# Camera.net
KiCad netlist of a schematic drawn in Altium Designer
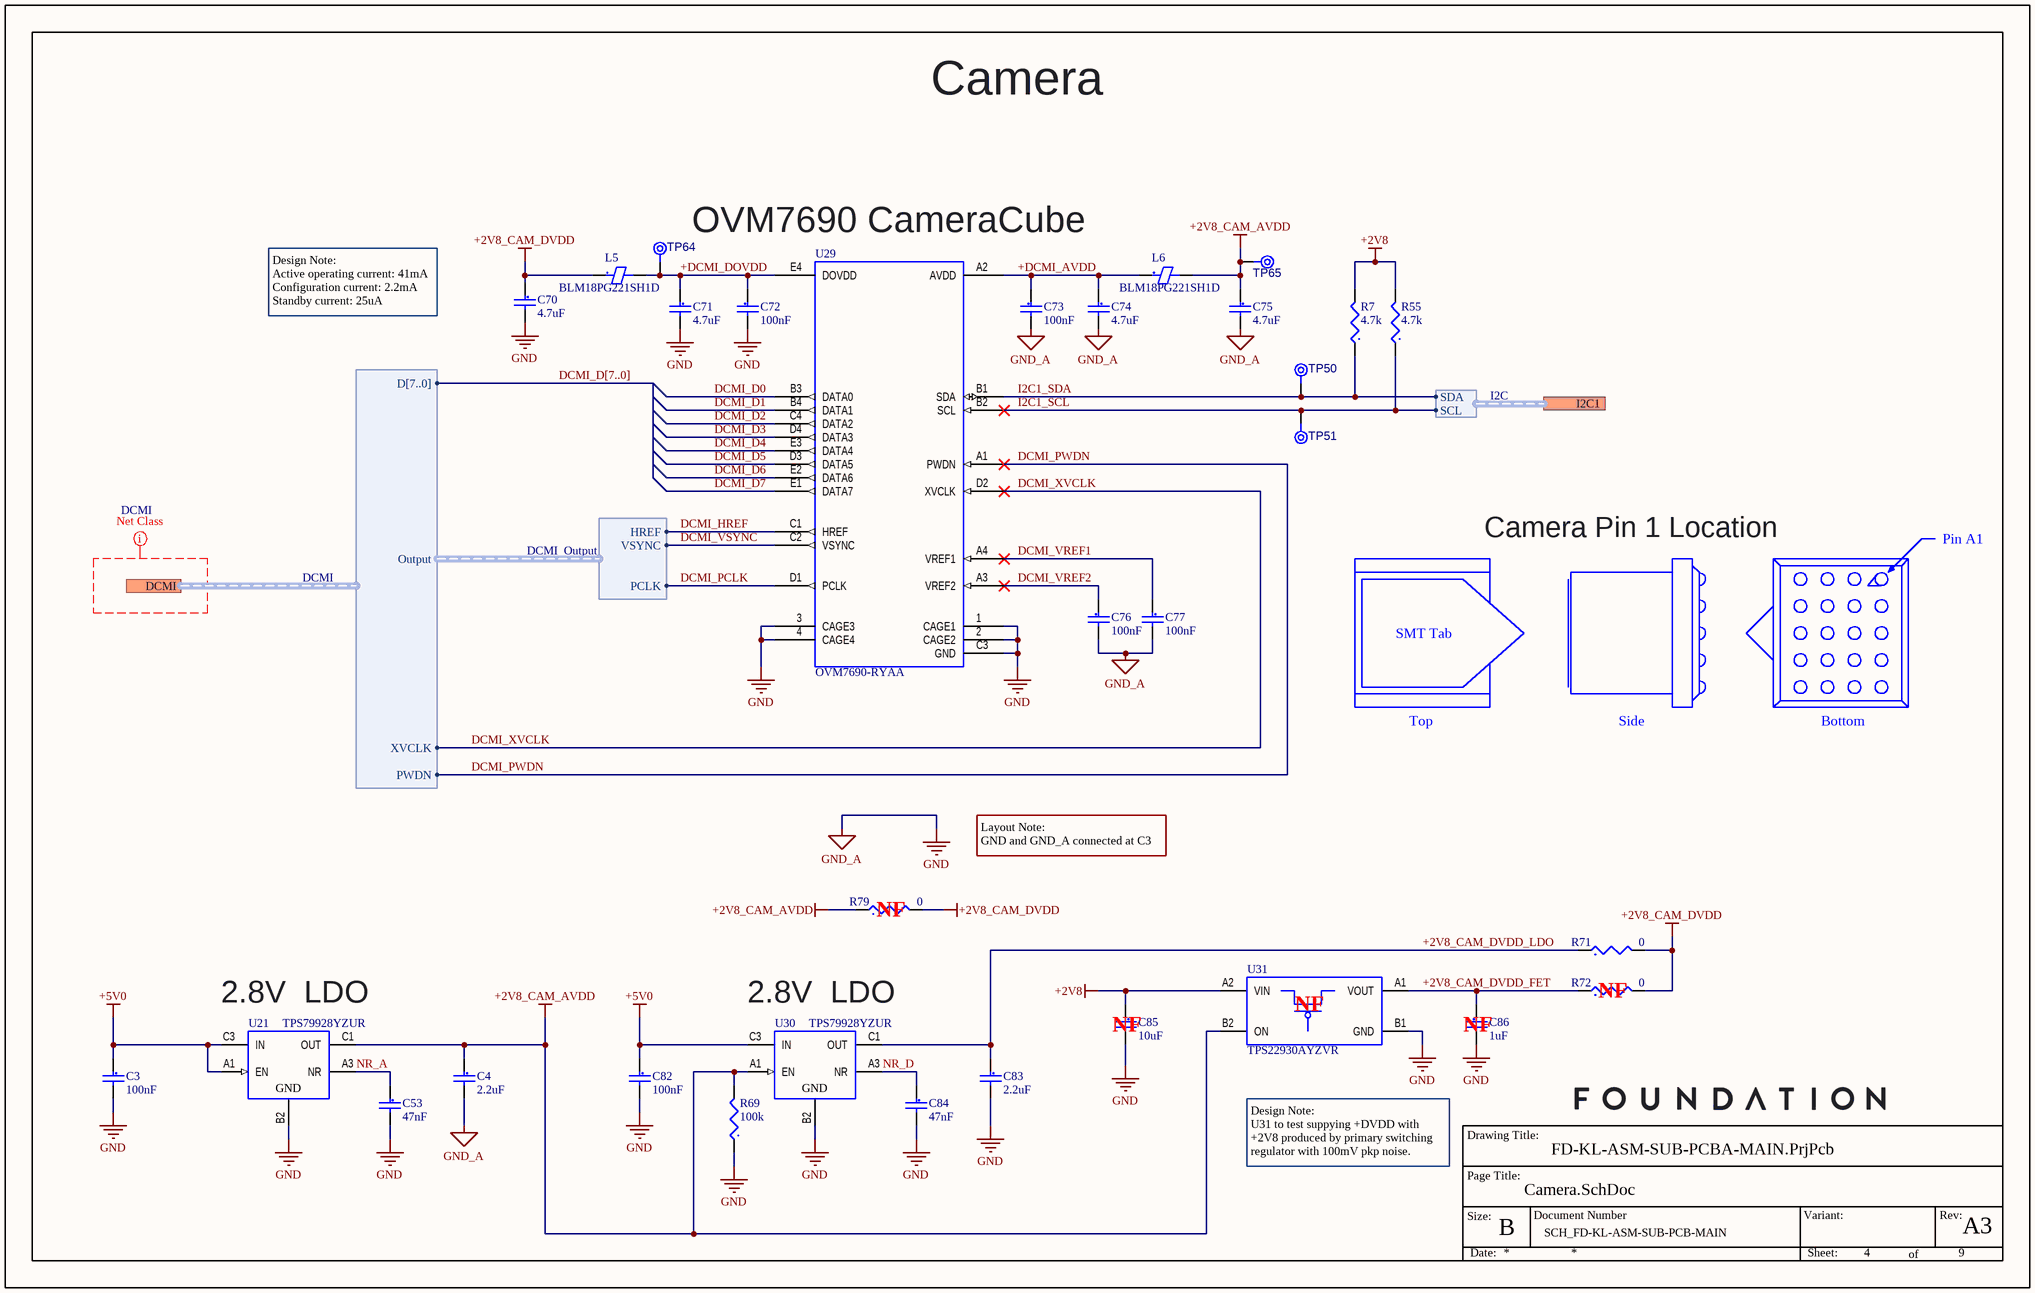
[diagram p0: Camera.SchDoc]

(export (version "E")
  (design (tool "Eeschema 10.0.6"))
  (components
    (comp (ref "C3")
      (value "CAP CER 0.1uF 16V 10% X7R 0402")
      (footprint "CAPC0402(1005)55_L")
      (description "0.1µF ±10% 16V Ceramic Capacitor X7R 0402 (1005 Metric)")
      (fields
        (field (name "CAPACITANCE") "100nF")
        (field (name "TOLERANCE") "10%")
        (field (name "VOLTAGE") "16V")
      )
      (libsource (lib "Altium Concord Pro on A365") (part "CAP-NP-2"))
    )
    (comp (ref "C4")
      (value "CAP CER 2.2uF 6.3V 10% X5R 0402")
      (footprint "CAPC0402(1005)55_L")
      (description "2.2µF ±10% 6.3V Ceramic Capacitor X5R 0402 (1005 Metric)")
      (fields (field (name "CAPACITANCE") "2.2uF") (field (name "TOLERANCE") "10%"))
      (libsource (lib "Altium Concord Pro on A365") (part "CAP-NP-2"))
    )
    (comp (ref "C53")
      (value "CAP CER 0.047uF 10V 10% X7R 0402")
      (footprint "CAPC0402(1005)55_L")
      (description "0.047µF ±10% 10V Ceramic Capacitor X7R 0402 (1005 Metric)")
      (fields (field (name "CAPACITANCE") "47nF"))
      (libsource (lib "Altium Concord Pro on A365") (part "CAP-NP-2"))
    )
    (comp (ref "C70")
      (value "CAP CER 4.7UF 10V 20% X5R 0402")
      (footprint "CAPC0402(1005)55_L")
      (description "4.7µF ±20% 10V Ceramic Capacitor X5R 0402 (1005 Metric)")
      (fields
        (field (name "CAPACITANCE") "4.7uF")
        (field (name "TOLERANCE") "20%")
        (field (name "VOLTAGE") "10V")
      )
      (libsource (lib "Altium Concord Pro on A365") (part "CAP-NP-2"))
    )
    (comp (ref "C71")
      (value "CAP CER 4.7UF 10V 20% X5R 0402")
      (footprint "CAPC0402(1005)55_L")
      (description "4.7µF ±20% 10V Ceramic Capacitor X5R 0402 (1005 Metric)")
      (fields
        (field (name "CAPACITANCE") "4.7uF")
        (field (name "TOLERANCE") "20%")
        (field (name "VOLTAGE") "10V")
      )
      (libsource (lib "Altium Concord Pro on A365") (part "CAP-NP-2"))
    )
    (comp (ref "C72")
      (value "CAP CER 0.1uF 16V 10% X7R 0402")
      (footprint "CAPC0402(1005)55_L")
      (description "0.1µF ±10% 16V Ceramic Capacitor X7R 0402 (1005 Metric)")
      (fields
        (field (name "CAPACITANCE") "100nF")
        (field (name "TOLERANCE") "10%")
        (field (name "VOLTAGE") "16V")
      )
      (libsource (lib "Altium Concord Pro on A365") (part "CAP-NP-2"))
    )
    (comp (ref "C73")
      (value "CAP CER 0.1uF 16V 10% X7R 0402")
      (footprint "CAPC0402(1005)55_L")
      (description "0.1µF ±10% 16V Ceramic Capacitor X7R 0402 (1005 Metric)")
      (fields
        (field (name "CAPACITANCE") "100nF")
        (field (name "TOLERANCE") "10%")
        (field (name "VOLTAGE") "16V")
      )
      (libsource (lib "Altium Concord Pro on A365") (part "CAP-NP-2"))
    )
    (comp (ref "C74")
      (value "CAP CER 4.7UF 10V 20% X5R 0402")
      (footprint "CAPC0402(1005)55_L")
      (description "4.7µF ±20% 10V Ceramic Capacitor X5R 0402 (1005 Metric)")
      (fields
        (field (name "CAPACITANCE") "4.7uF")
        (field (name "TOLERANCE") "20%")
        (field (name "VOLTAGE") "10V")
      )
      (libsource (lib "Altium Concord Pro on A365") (part "CAP-NP-2"))
    )
    (comp (ref "C75")
      (value "CAP CER 4.7UF 10V 20% X5R 0402")
      (footprint "CAPC0402(1005)55_L")
      (description "4.7µF ±20% 10V Ceramic Capacitor X5R 0402 (1005 Metric)")
      (fields
        (field (name "CAPACITANCE") "4.7uF")
        (field (name "TOLERANCE") "20%")
        (field (name "VOLTAGE") "10V")
      )
      (libsource (lib "Altium Concord Pro on A365") (part "CAP-NP-2"))
    )
    (comp (ref "C76")
      (value "CAP CER 0.1uF 16V 10% X7R 0402")
      (footprint "CAPC0402(1005)55_L")
      (description "0.1µF ±10% 16V Ceramic Capacitor X7R 0402 (1005 Metric)")
      (fields
        (field (name "CAPACITANCE") "100nF")
        (field (name "TOLERANCE") "10%")
        (field (name "VOLTAGE") "16V")
      )
      (libsource (lib "Altium Concord Pro on A365") (part "CAP-NP-2"))
    )
    (comp (ref "C77")
      (value "CAP CER 0.1uF 16V 10% X7R 0402")
      (footprint "CAPC0402(1005)55_L")
      (description "0.1µF ±10% 16V Ceramic Capacitor X7R 0402 (1005 Metric)")
      (fields
        (field (name "CAPACITANCE") "100nF")
        (field (name "TOLERANCE") "10%")
        (field (name "VOLTAGE") "16V")
      )
      (libsource (lib "Altium Concord Pro on A365") (part "CAP-NP-2"))
    )
    (comp (ref "C82")
      (value "CAP CER 0.1uF 16V 10% X7R 0402")
      (footprint "CAPC0402(1005)55_L")
      (description "0.1µF ±10% 16V Ceramic Capacitor X7R 0402 (1005 Metric)")
      (fields
        (field (name "CAPACITANCE") "100nF")
        (field (name "TOLERANCE") "10%")
        (field (name "VOLTAGE") "16V")
      )
      (libsource (lib "Altium Concord Pro on A365") (part "CAP-NP-2"))
    )
    (comp (ref "C83")
      (value "CAP CER 2.2uF 6.3V 10% X5R 0402")
      (footprint "CAPC0402(1005)55_L")
      (description "2.2µF ±10% 6.3V Ceramic Capacitor X5R 0402 (1005 Metric)")
      (fields (field (name "CAPACITANCE") "2.2uF") (field (name "TOLERANCE") "10%"))
      (libsource (lib "Altium Concord Pro on A365") (part "CAP-NP-2"))
    )
    (comp (ref "C84")
      (value "CAP CER 0.047uF 10V 10% X7R 0402")
      (footprint "CAPC0402(1005)55_L")
      (description "0.047µF ±10% 10V Ceramic Capacitor X7R 0402 (1005 Metric)")
      (fields (field (name "CAPACITANCE") "47nF"))
      (libsource (lib "Altium Concord Pro on A365") (part "CAP-NP-2"))
    )
    (comp (ref "C85")
      (value "CAP CER 10uF 10V 20% X5R 0402")
      (footprint "CAPC0402(1005)55_L")
      (description "10µF ±20% 10V Ceramic Capacitor X5R 0402 (1005 Metric)")
      (fields (field (name "CAPACITANCE") "10uF") (field (name "TOLERANCE") "20%"))
      (libsource (lib "Altium Concord Pro on A365") (part "CAP-NP-2"))
    )
    (comp (ref "C86")
      (value "CAP CER 1uF 25V 10% X5R 0402")
      (footprint "CAPC0402(1005)55_L")
      (description "1uF ±10% 25V Ceramic Capacitor X5R 0402 (1005 Metric)")
      (fields (field (name "CAPACITANCE") "1uF"))
      (libsource (lib "Altium Concord Pro on A365") (part "CAP-NP-2"))
    )
    (comp (ref "L5")
      (value "BLM18PG221SH1D")
      (footprint "FBC0603(1608)90_L")
      (description "FERRITE BEAD 220 OHM 0603 1LN")
      (fields (field (name "TOLERANCE") "25%"))
      (libsource (lib "Altium Concord Pro on A365") (part "FB-NP-2"))
    )
    (comp (ref "L6")
      (value "BLM18PG221SH1D")
      (footprint "FBC0603(1608)90_L")
      (description "FERRITE BEAD 220 OHM 0603 1LN")
      (fields (field (name "TOLERANCE") "25%"))
      (libsource (lib "Altium Concord Pro on A365") (part "FB-NP-2"))
    )
    (comp (ref "R7")
      (value "RES 4.7K 1/16W 1% 0402")
      (footprint "RESC0402(1005)_L")
      (description "4.7 kOhms ±1% 0.063W, 1/16W Chip Resistor 0402 (1005 Metric) Automotive AEC-Q200 Thick Film")
      (fields (field (name "RESISTANCE") "4.7k") (field (name "TOLERANCE") "1%"))
      (libsource (lib "Altium Concord Pro on A365") (part "RES-2"))
    )
    (comp (ref "R55")
      (value "RES 4.7K 1/16W 1% 0402")
      (footprint "RESC0402(1005)_L")
      (description "4.7 kOhms ±1% 0.063W, 1/16W Chip Resistor 0402 (1005 Metric) Automotive AEC-Q200 Thick Film")
      (fields (field (name "RESISTANCE") "4.7k") (field (name "TOLERANCE") "1%"))
      (libsource (lib "Altium Concord Pro on A365") (part "RES-2"))
    )
    (comp (ref "R69")
      (value "RES 100K 1/16W 1% 0402")
      (footprint "RESC0402(1005)_L")
      (description "100 kOhms ±1% 0.063W, 1/16W Chip Resistor 0402 (1005 Metric) Automotive AEC-Q200 Thick Film")
      (fields (field (name "RESISTANCE") "100k") (field (name "TOLERANCE") "1%"))
      (libsource (lib "Altium Concord Pro on A365") (part "RES-2"))
    )
    (comp (ref "R71")
      (value "RES 0 OHM JUMPER 1/10W 0603")
      (footprint "RESC0603(1608)_L")
      (description "0 Ohms Jumper 0.1W, 1/10W Chip Resistor 0603 (1608 Metric)")
      (fields (field (name "RESISTANCE") "0") (field (name "TOLERANCE") "1%"))
      (libsource (lib "Altium Concord Pro on A365") (part "RES-2"))
    )
    (comp (ref "R72")
      (value "RES 0 OHM JUMPER 1/10W 0603")
      (footprint "RESC0603(1608)_L")
      (description "0 Ohms Jumper 0.1W, 1/10W Chip Resistor 0603 (1608 Metric)")
      (fields (field (name "RESISTANCE") "0") (field (name "TOLERANCE") "1%"))
      (libsource (lib "Altium Concord Pro on A365") (part "RES-2"))
    )
    (comp (ref "R79")
      (value "RES 0 OHM JUMPER 1/10W 0603")
      (footprint "RESC0603(1608)_L")
      (description "0 Ohms Jumper 0.1W, 1/10W Chip Resistor 0603 (1608 Metric)")
      (fields (field (name "RESISTANCE") "0") (field (name "TOLERANCE") "1%"))
      (libsource (lib "Altium Concord Pro on A365") (part "RES-2"))
    )
    (comp (ref "TP50")
      (value "TPAD8R")
      (footprint "TP08R")
      (description "0.8mm round")
      (libsource (lib "Altium Concord Pro on A365") (part "TP-R-1"))
    )
    (comp (ref "TP51")
      (value "TPAD8R")
      (footprint "TP08R")
      (description "0.8mm round")
      (libsource (lib "Altium Concord Pro on A365") (part "TP-R-1"))
    )
    (comp (ref "TP64")
      (value "TPAD8R")
      (footprint "TP08R")
      (description "0.8mm round")
      (libsource (lib "Altium Concord Pro on A365") (part "TP-R-1"))
    )
    (comp (ref "TP65")
      (value "TPAD8R")
      (footprint "TP08R")
      (description "0.8mm round")
      (libsource (lib "Altium Concord Pro on A365") (part "TP-R-1"))
    )
    (comp (ref "U21")
      (value "TPS79928YZUR")
      (footprint "TI - DSBGA-YZU-5_V")
      (description "Linear Voltage Regulator IC  1 Output  200mA 5-DSBGA (1x1.37)")
      (libsource (lib "Altium Concord Pro on A365") (part "TPS79928YZU"))
    )
    (comp (ref "U29")
      (value "OVM7690-RYAA")
      (footprint "OMNI - CCBGA-CG-20")
      (description "SENSOR CAMERA CMOS 20CAMERACUBE")
      (libsource (lib "Altium Concord Pro on A365") (part "OVM7690-RYAA"))
    )
    (comp (ref "U30")
      (value "TPS79928YZUR")
      (footprint "TI - DSBGA-YZU-5_V")
      (description "Linear Voltage Regulator IC  1 Output  200mA 5-DSBGA (1x1.37)")
      (libsource (lib "Altium Concord Pro on A365") (part "TPS79928YZU"))
    )
    (comp (ref "U31")
      (value "TPS22930AYZVR")
      (footprint "TI - DSBGA-YZV-4_V")
      (description "IC PWR SWITCH P-CHAN 1:1 4DSBGA")
      (libsource (lib "Altium Concord Pro on A365") (part "TPS22930AYZVR"))
    )
  )
  (nets
    (net (code "4") (name "+2V8") (class "Default")
      (node (ref "C85") (pin "1") (pinfunction "1_1") (pintype "passive"))
      (node (ref "R55") (pin "2") (pinfunction "2_2") (pintype "passive"))
      (node (ref "R7") (pin "2") (pinfunction "2_2") (pintype "passive"))
      (node (ref "U31") (pin "A2") (pinfunction "VIN_A2") (pintype "passive"))
    )
    (net (code "5") (name "+2V8_CAM_AVDD") (class "Default")
      (node (ref "C4") (pin "1") (pinfunction "1_1") (pintype "passive"))
      (node (ref "C75") (pin "1") (pinfunction "1_1") (pintype "passive"))
      (node (ref "L6") (pin "2") (pinfunction "2_2") (pintype "passive"))
      (node (ref "R69") (pin "2") (pinfunction "2_2") (pintype "passive"))
      (node (ref "R79") (pin "1") (pinfunction "1_1") (pintype "passive"))
      (node (ref "TP65") (pin "1") (pinfunction "TP_1") (pintype "passive"))
      (node (ref "U21") (pin "C1") (pinfunction "OUT_C1") (pintype "power_in"))
      (node (ref "U30") (pin "A1") (pinfunction "EN_A1") (pintype "input"))
      (node (ref "U31") (pin "B2") (pinfunction "ON_B2") (pintype "passive"))
    )
    (net (code "6") (name "+2V8_CAM_DVDD") (class "Default")
      (node (ref "C70") (pin "1") (pinfunction "1_1") (pintype "passive"))
      (node (ref "L5") (pin "1") (pinfunction "1_1") (pintype "passive"))
      (node (ref "R71") (pin "2") (pinfunction "2_2") (pintype "passive"))
      (node (ref "R72") (pin "2") (pinfunction "2_2") (pintype "passive"))
      (node (ref "R79") (pin "2") (pinfunction "2_2") (pintype "passive"))
    )
    (net (code "7") (name "+5V0") (class "Default")
      (node (ref "C3") (pin "1") (pinfunction "1_1") (pintype "passive"))
      (node (ref "C82") (pin "1") (pinfunction "1_1") (pintype "passive"))
      (node (ref "U21") (pin "A1") (pinfunction "EN_A1") (pintype "input"))
      (node (ref "U21") (pin "C3") (pinfunction "IN_C3") (pintype "power_in"))
      (node (ref "U30") (pin "C3") (pinfunction "IN_C3") (pintype "power_in"))
    )
    (net (code "8") (name "/+2V8_CAM_DVDD_FET") (class "Default")
      (node (ref "C86") (pin "1") (pinfunction "1_1") (pintype "passive"))
      (node (ref "R72") (pin "1") (pinfunction "1_1") (pintype "passive"))
      (node (ref "U31") (pin "A1") (pinfunction "VOUT_A1") (pintype "passive"))
    )
    (net (code "9") (name "/+2V8_CAM_DVDD_LDO") (class "Default")
      (node (ref "C83") (pin "1") (pinfunction "1_1") (pintype "passive"))
      (node (ref "R71") (pin "1") (pinfunction "1_1") (pintype "passive"))
      (node (ref "U30") (pin "C1") (pinfunction "OUT_C1") (pintype "power_in"))
    )
    (net (code "10") (name "/+DCMI_AVDD") (class "Default")
      (node (ref "C73") (pin "1") (pinfunction "1_1") (pintype "passive"))
      (node (ref "C74") (pin "1") (pinfunction "1_1") (pintype "passive"))
      (node (ref "L6") (pin "1") (pinfunction "1_1") (pintype "passive"))
      (node (ref "U29") (pin "A2") (pinfunction "AVDD_A2") (pintype "power_in"))
    )
    (net (code "11") (name "/+DCMI_DOVDD") (class "Default")
      (node (ref "C71") (pin "1") (pinfunction "1_1") (pintype "passive"))
      (node (ref "C72") (pin "1") (pinfunction "1_1") (pintype "passive"))
      (node (ref "L5") (pin "2") (pinfunction "2_2") (pintype "passive"))
      (node (ref "TP64") (pin "1") (pinfunction "TP_1") (pintype "passive"))
      (node (ref "U29") (pin "E4") (pinfunction "DOVDD_E4") (pintype "power_in"))
    )
    (net (code "12") (name "/DCMI_D0") (class "Default")
      (node (ref "U29") (pin "B3") (pinfunction "DATA0_B3") (pintype "output"))
    )
    (net (code "13") (name "/DCMI_D1") (class "Default")
      (node (ref "U29") (pin "B4") (pinfunction "DATA1_B4") (pintype "output"))
    )
    (net (code "14") (name "/DCMI_D2") (class "Default")
      (node (ref "U29") (pin "C4") (pinfunction "DATA2_C4") (pintype "output"))
    )
    (net (code "15") (name "/DCMI_D3") (class "Default")
      (node (ref "U29") (pin "D4") (pinfunction "DATA3_D4") (pintype "output"))
    )
    (net (code "16") (name "/DCMI_D4") (class "Default")
      (node (ref "U29") (pin "E3") (pinfunction "DATA4_E3") (pintype "output"))
    )
    (net (code "17") (name "/DCMI_D5") (class "Default")
      (node (ref "U29") (pin "D3") (pinfunction "DATA5_D3") (pintype "output"))
    )
    (net (code "18") (name "/DCMI_D6") (class "Default")
      (node (ref "U29") (pin "E2") (pinfunction "DATA6_E2") (pintype "output"))
    )
    (net (code "19") (name "/DCMI_D7") (class "Default")
      (node (ref "U29") (pin "E1") (pinfunction "DATA7_E1") (pintype "output"))
    )
    (net (code "21") (name "/DCMI_HREF") (class "Default")
      (node (ref "U29") (pin "C1") (pinfunction "HREF_C1") (pintype "output"))
    )
    (net (code "22") (name "/DCMI_PCLK") (class "Default")
      (node (ref "U29") (pin "D1") (pinfunction "PCLK_D1") (pintype "output"))
    )
    (net (code "23") (name "/DCMI_PWDN") (class "Default")
      (node (ref "U29") (pin "A1") (pinfunction "PWDN_A1") (pintype "input+no_connect"))
    )
    (net (code "24") (name "/DCMI_VREF1") (class "Default")
      (node (ref "C77") (pin "1") (pinfunction "1_1") (pintype "passive"))
      (node (ref "U29") (pin "A4") (pinfunction "VREF1_A4") (pintype "input"))
    )
    (net (code "25") (name "/DCMI_VREF2") (class "Default")
      (node (ref "C76") (pin "1") (pinfunction "1_1") (pintype "passive"))
      (node (ref "U29") (pin "A3") (pinfunction "VREF2_A3") (pintype "input"))
    )
    (net (code "26") (name "/DCMI_VSYNC") (class "Default")
      (node (ref "U29") (pin "C2") (pinfunction "VSYNC_C2") (pintype "output"))
    )
    (net (code "27") (name "/DCMI_XVCLK") (class "Default")
      (node (ref "U29") (pin "D2") (pinfunction "XVCLK_D2") (pintype "input+no_connect"))
    )
    (net (code "29") (name "/I2C1_SCL") (class "Default")
      (node (ref "R55") (pin "1") (pinfunction "1_1") (pintype "passive"))
      (node (ref "TP51") (pin "1") (pinfunction "TP_1") (pintype "passive"))
      (node (ref "U29") (pin "B2") (pinfunction "SCL_B2") (pintype "input"))
    )
    (net (code "30") (name "/I2C1_SDA") (class "Default")
      (node (ref "R7") (pin "1") (pinfunction "1_1") (pintype "passive"))
      (node (ref "TP50") (pin "1") (pinfunction "TP_1") (pintype "passive"))
      (node (ref "U29") (pin "B1") (pinfunction "SDA_B1") (pintype "bidirectional"))
    )
    (net (code "31") (name "/NR_A") (class "Default")
      (node (ref "C53") (pin "1") (pinfunction "1_1") (pintype "passive"))
      (node (ref "U21") (pin "A3") (pinfunction "NR_A3") (pintype "passive"))
    )
    (net (code "32") (name "/NR_D") (class "Default")
      (node (ref "C84") (pin "1") (pinfunction "1_1") (pintype "passive"))
      (node (ref "U30") (pin "A3") (pinfunction "NR_A3") (pintype "passive"))
    )
    (net (code "35") (name "GND") (class "Default")
      (node (ref "C3") (pin "2") (pinfunction "2_2") (pintype "passive"))
      (node (ref "C4") (pin "2") (pinfunction "2_2") (pintype "passive"))
      (node (ref "C53") (pin "2") (pinfunction "2_2") (pintype "passive"))
      (node (ref "C70") (pin "2") (pinfunction "2_2") (pintype "passive"))
      (node (ref "C71") (pin "2") (pinfunction "2_2") (pintype "passive"))
      (node (ref "C72") (pin "2") (pinfunction "2_2") (pintype "passive"))
      (node (ref "C73") (pin "2") (pinfunction "2_2") (pintype "passive"))
      (node (ref "C74") (pin "2") (pinfunction "2_2") (pintype "passive"))
      (node (ref "C75") (pin "2") (pinfunction "2_2") (pintype "passive"))
      (node (ref "C76") (pin "2") (pinfunction "2_2") (pintype "passive"))
      (node (ref "C77") (pin "2") (pinfunction "2_2") (pintype "passive"))
      (node (ref "C82") (pin "2") (pinfunction "2_2") (pintype "passive"))
      (node (ref "C83") (pin "2") (pinfunction "2_2") (pintype "passive"))
      (node (ref "C84") (pin "2") (pinfunction "2_2") (pintype "passive"))
      (node (ref "C85") (pin "2") (pinfunction "2_2") (pintype "passive"))
      (node (ref "C86") (pin "2") (pinfunction "2_2") (pintype "passive"))
      (node (ref "R69") (pin "1") (pinfunction "1_1") (pintype "passive"))
      (node (ref "U21") (pin "B2") (pinfunction "GND_B2") (pintype "power_in"))
      (node (ref "U29") (pin "1") (pinfunction "CAGE1_1") (pintype "power_in"))
      (node (ref "U29") (pin "2") (pinfunction "CAGE2_2") (pintype "power_in"))
      (node (ref "U29") (pin "3") (pinfunction "CAGE3_3") (pintype "power_in"))
      (node (ref "U29") (pin "4") (pinfunction "CAGE4_4") (pintype "power_in"))
      (node (ref "U29") (pin "C3") (pinfunction "GND_C3") (pintype "power_in"))
      (node (ref "U30") (pin "B2") (pinfunction "GND_B2") (pintype "power_in"))
      (node (ref "U31") (pin "B1") (pinfunction "GND_B1") (pintype "passive"))
    )
  )
)
